# untitled.net
KiCad netlist of a schematic drawn in EAGLE
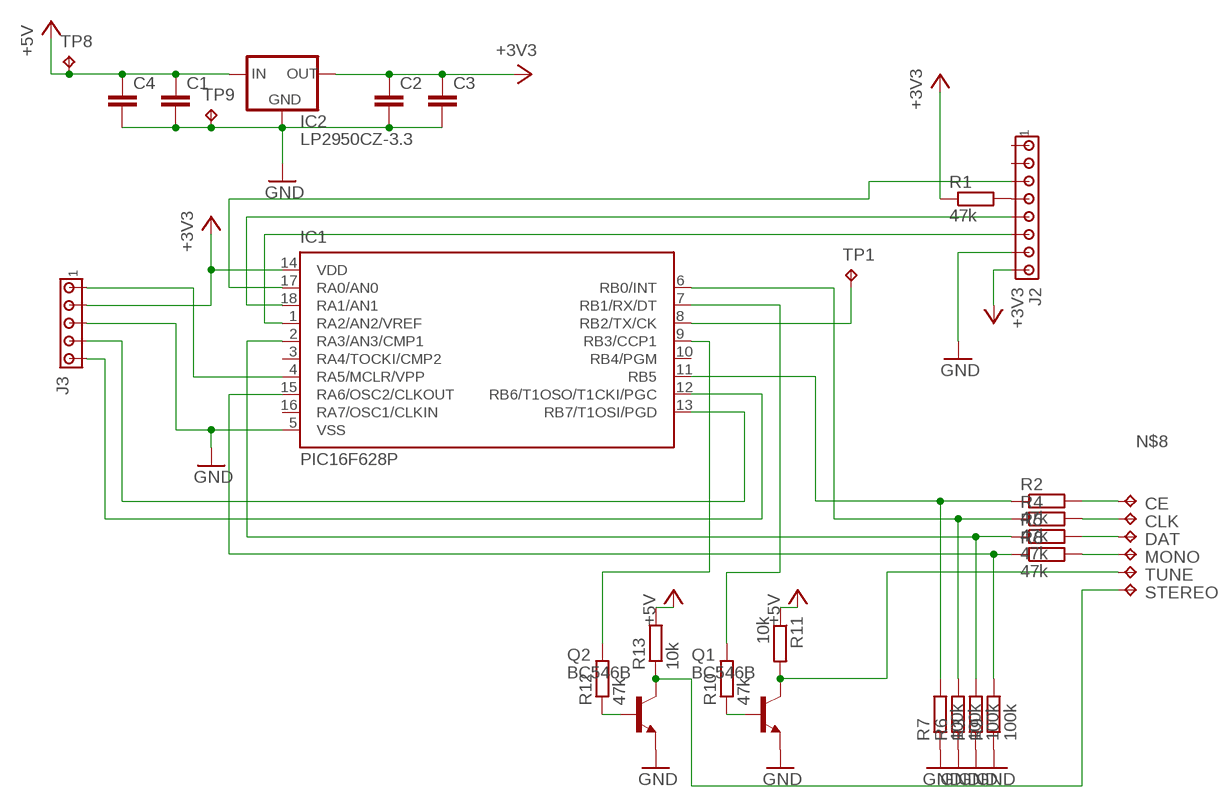
[diagram p0: schematic, sheet 1]

(export (version "E")
  (design (tool "Eeschema 10.0.6"))
  (components
    (comp (ref "C1")
      (value "C-EU025-024X044")
      (footprint "eagle-import:C025-024X044")
      (libsource (lib "eagle-import") (part "C-EU025-024X044"))
    )
    (comp (ref "C2")
      (value "C-EU025-024X044")
      (footprint "eagle-import:C025-024X044")
      (libsource (lib "eagle-import") (part "C-EU025-024X044"))
    )
    (comp (ref "C3")
      (value "C-EU025-024X044")
      (footprint "eagle-import:C025-024X044")
      (libsource (lib "eagle-import") (part "C-EU025-024X044"))
    )
    (comp (ref "C4")
      (value "C-EU025-024X044")
      (footprint "eagle-import:C025-024X044")
      (libsource (lib "eagle-import") (part "C-EU025-024X044"))
    )
    (comp (ref "CE")
      (value "TPB1,27")
      (footprint "eagle-import:B1,27")
      (libsource (lib "eagle-import") (part "TPB1,27"))
    )
    (comp (ref "CLK")
      (value "TPB1,27")
      (footprint "eagle-import:B1,27")
      (libsource (lib "eagle-import") (part "TPB1,27"))
    )
    (comp (ref "DAT")
      (value "TPB1,27")
      (footprint "eagle-import:B1,27")
      (libsource (lib "eagle-import") (part "TPB1,27"))
    )
    (comp (ref "IC1")
      (value "PIC16F628P")
      (footprint "eagle-import:DIL18")
      (fields (field (name "MF") "MICROCHIP") (field (name "MPN") "PIC16F628-04I/P"))
      (libsource (lib "eagle-import") (part "PIC16F62P8"))
    )
    (comp (ref "IC2")
      (value "LP2950CZ-3.3")
      (footprint "eagle-import:TO92")
      (libsource (lib "eagle-import") (part "LP2950?CZ-3.3"))
    )
    (comp (ref "J2")
      (value "MTA08-100")
      (footprint "eagle-import:10X08MTA")
      (libsource (lib "eagle-import") (part "MTA08-100"))
    )
    (comp (ref "J3")
      (value "MTA05-100")
      (footprint "eagle-import:10X05MTA")
      (libsource (lib "eagle-import") (part "MTA05-100"))
    )
    (comp (ref "MONO")
      (value "TPB1,27")
      (footprint "eagle-import:B1,27")
      (libsource (lib "eagle-import") (part "TPB1,27"))
    )
    (comp (ref "Q1")
      (value "BC546B")
      (footprint "eagle-import:TO92-EBC")
      (libsource (lib "eagle-import") (part "BC546B"))
    )
    (comp (ref "Q2")
      (value "BC546B")
      (footprint "eagle-import:TO92-EBC")
      (libsource (lib "eagle-import") (part "BC546B"))
    )
    (comp (ref "R1")
      (value "47k")
      (footprint "eagle-import:0204_7")
      (libsource (lib "eagle-import") (part "R-EU_0204/7"))
    )
    (comp (ref "R2")
      (value "47k")
      (footprint "eagle-import:0204_7")
      (libsource (lib "eagle-import") (part "R-EU_0204/7"))
    )
    (comp (ref "R3")
      (value "100k")
      (footprint "eagle-import:0204_7")
      (libsource (lib "eagle-import") (part "R-EU_0204/7"))
    )
    (comp (ref "R4")
      (value "47k")
      (footprint "eagle-import:0204_7")
      (libsource (lib "eagle-import") (part "R-EU_0204/7"))
    )
    (comp (ref "R5")
      (value "47k")
      (footprint "eagle-import:0204_7")
      (libsource (lib "eagle-import") (part "R-EU_0204/7"))
    )
    (comp (ref "R6")
      (value "100k")
      (footprint "eagle-import:0204_7")
      (libsource (lib "eagle-import") (part "R-EU_0204/7"))
    )
    (comp (ref "R7")
      (value "100k")
      (footprint "eagle-import:0204_7")
      (libsource (lib "eagle-import") (part "R-EU_0204/7"))
    )
    (comp (ref "R8")
      (value "47k")
      (footprint "eagle-import:0204_7")
      (libsource (lib "eagle-import") (part "R-EU_0204/7"))
    )
    (comp (ref "R9")
      (value "100k")
      (footprint "eagle-import:0204_7")
      (libsource (lib "eagle-import") (part "R-EU_0204/7"))
    )
    (comp (ref "R10")
      (value "47k")
      (footprint "eagle-import:0204_7")
      (libsource (lib "eagle-import") (part "R-EU_0204/7"))
    )
    (comp (ref "R11")
      (value "10k")
      (footprint "eagle-import:0204_7")
      (libsource (lib "eagle-import") (part "R-EU_0204/7"))
    )
    (comp (ref "R12")
      (value "47k")
      (footprint "eagle-import:0204_7")
      (libsource (lib "eagle-import") (part "R-EU_0204/7"))
    )
    (comp (ref "R13")
      (value "10k")
      (footprint "eagle-import:0204_7")
      (libsource (lib "eagle-import") (part "R-EU_0204/7"))
    )
    (comp (ref "STEREO")
      (value "TPB1,27")
      (footprint "eagle-import:B1,27")
      (libsource (lib "eagle-import") (part "TPB1,27"))
    )
    (comp (ref "TP1")
      (value "TPB1,27")
      (footprint "eagle-import:B1,27")
      (libsource (lib "eagle-import") (part "TPB1,27"))
    )
    (comp (ref "TP8")
      (value "TPB1,27")
      (footprint "eagle-import:B1,27")
      (libsource (lib "eagle-import") (part "TPB1,27"))
    )
    (comp (ref "TP9")
      (value "TPB1,27")
      (footprint "eagle-import:B1,27")
      (libsource (lib "eagle-import") (part "TPB1,27"))
    )
    (comp (ref "TUNE")
      (value "TPB1,27")
      (footprint "eagle-import:B1,27")
      (libsource (lib "eagle-import") (part "TPB1,27"))
    )
  )
  (nets
    (net (code "1") (name "+3V3") (class "Default")
      (node (ref "C2") (pin "1") (pinfunction "1_1") (pintype "passive"))
      (node (ref "C3") (pin "1") (pinfunction "1_1") (pintype "passive"))
      (node (ref "IC1") (pin "14") (pinfunction "VDD_14") (pintype "power_in"))
      (node (ref "IC2") (pin "1") (pinfunction "OUT_1") (pintype "passive"))
      (node (ref "J2") (pin "8") (pinfunction "8_8") (pintype "passive"))
      (node (ref "J3") (pin "2") (pinfunction "2_2") (pintype "passive"))
      (node (ref "R1") (pin "1") (pinfunction "1_1") (pintype "passive"))
    )
    (net (code "2") (name "+5V") (class "Default")
      (node (ref "C1") (pin "1") (pinfunction "1_1") (pintype "passive"))
      (node (ref "C4") (pin "1") (pinfunction "1_1") (pintype "passive"))
      (node (ref "IC2") (pin "3") (pinfunction "IN_3") (pintype "input"))
      (node (ref "R11") (pin "1") (pinfunction "1_1") (pintype "passive"))
      (node (ref "R13") (pin "2") (pinfunction "2_2") (pintype "passive"))
      (node (ref "TP8") (pin "TP") (pinfunction "TP_TP") (pintype "input"))
    )
    (net (code "3") (name "/N$8") (class "Default")
      (node (ref "CE") (pin "TP") (pinfunction "TP_TP") (pintype "input"))
      (node (ref "R2") (pin "2") (pinfunction "2_2") (pintype "passive"))
    )
    (net (code "4") (name "GND") (class "Default")
      (node (ref "C1") (pin "2") (pinfunction "2_2") (pintype "passive"))
      (node (ref "C2") (pin "2") (pinfunction "2_2") (pintype "passive"))
      (node (ref "C3") (pin "2") (pinfunction "2_2") (pintype "passive"))
      (node (ref "C4") (pin "2") (pinfunction "2_2") (pintype "passive"))
      (node (ref "IC1") (pin "5") (pinfunction "VSS_5") (pintype "power_in"))
      (node (ref "IC2") (pin "2") (pinfunction "GND_2") (pintype "input"))
      (node (ref "J2") (pin "7") (pinfunction "7_7") (pintype "passive"))
      (node (ref "J3") (pin "3") (pinfunction "3_3") (pintype "passive"))
      (node (ref "Q1") (pin "E") (pinfunction "E_E") (pintype "passive"))
      (node (ref "Q2") (pin "E") (pinfunction "E_E") (pintype "passive"))
      (node (ref "R3") (pin "1") (pinfunction "1_1") (pintype "passive"))
      (node (ref "R6") (pin "1") (pinfunction "1_1") (pintype "passive"))
      (node (ref "R7") (pin "1") (pinfunction "1_1") (pintype "passive"))
      (node (ref "R9") (pin "1") (pinfunction "1_1") (pintype "passive"))
      (node (ref "TP9") (pin "TP") (pinfunction "TP_TP") (pintype "input"))
    )
    (net (code "5") (name "Net-(CLK-PadTP)") (class "Default")
      (node (ref "CLK") (pin "TP") (pinfunction "TP_TP") (pintype "input"))
      (node (ref "R4") (pin "2") (pinfunction "2_2") (pintype "passive"))
    )
    (net (code "6") (name "Net-(DAT-PadTP)") (class "Default")
      (node (ref "DAT") (pin "TP") (pinfunction "TP_TP") (pintype "input"))
      (node (ref "R5") (pin "2") (pinfunction "2_2") (pintype "passive"))
    )
    (net (code "7") (name "Net-(IC1-RA0{slash}AN0)") (class "Default")
      (node (ref "IC1") (pin "17") (pinfunction "RA0/AN0_17") (pintype "bidirectional"))
      (node (ref "J2") (pin "3") (pinfunction "3_3") (pintype "passive"))
    )
    (net (code "8") (name "Net-(IC1-RA1{slash}AN1)") (class "Default")
      (node (ref "IC1") (pin "18") (pinfunction "RA1/AN1_18") (pintype "bidirectional"))
      (node (ref "J2") (pin "5") (pinfunction "5_5") (pintype "passive"))
    )
    (net (code "9") (name "Net-(IC1-RA2{slash}AN2{slash}VREF)") (class "Default")
      (node (ref "IC1") (pin "1") (pinfunction "RA2/AN2/VREF_1") (pintype "bidirectional"))
      (node (ref "J2") (pin "6") (pinfunction "6_6") (pintype "passive"))
    )
    (net (code "10") (name "Net-(IC1-RA3{slash}AN3{slash}CMP1)") (class "Default")
      (node (ref "IC1") (pin "2") (pinfunction "RA3/AN3/CMP1_2") (pintype "bidirectional"))
      (node (ref "R3") (pin "2") (pinfunction "2_2") (pintype "passive"))
      (node (ref "R5") (pin "1") (pinfunction "1_1") (pintype "passive"))
    )
    (net (code "11") (name "Net-(IC1-RA5{slash}MCLR{slash}VPP)") (class "Default")
      (node (ref "IC1") (pin "4") (pinfunction "RA5/MCLR/VPP_4") (pintype "bidirectional"))
      (node (ref "J3") (pin "1") (pinfunction "1_1") (pintype "passive"))
    )
    (net (code "12") (name "Net-(IC1-RA6{slash}OSC2{slash}CLKOUT)") (class "Default")
      (node (ref "IC1") (pin "15") (pinfunction "RA6/OSC2/CLKOUT_15") (pintype "bidirectional"))
      (node (ref "R8") (pin "1") (pinfunction "1_1") (pintype "passive"))
      (node (ref "R9") (pin "2") (pinfunction "2_2") (pintype "passive"))
    )
    (net (code "13") (name "Net-(IC1-RB0{slash}INT)") (class "Default")
      (node (ref "IC1") (pin "6") (pinfunction "RB0/INT_6") (pintype "bidirectional"))
      (node (ref "R4") (pin "1") (pinfunction "1_1") (pintype "passive"))
      (node (ref "R6") (pin "2") (pinfunction "2_2") (pintype "passive"))
    )
    (net (code "14") (name "Net-(IC1-RB1{slash}RX{slash}DT)") (class "Default")
      (node (ref "IC1") (pin "7") (pinfunction "RB1/RX/DT_7") (pintype "bidirectional"))
      (node (ref "R10") (pin "2") (pinfunction "2_2") (pintype "passive"))
    )
    (net (code "15") (name "Net-(IC1-RB2{slash}TX{slash}CK)") (class "Default")
      (node (ref "IC1") (pin "8") (pinfunction "RB2/TX/CK_8") (pintype "bidirectional"))
      (node (ref "TP1") (pin "TP") (pinfunction "TP_TP") (pintype "input"))
    )
    (net (code "16") (name "Net-(IC1-RB3{slash}CCP1)") (class "Default")
      (node (ref "IC1") (pin "9") (pinfunction "RB3/CCP1_9") (pintype "bidirectional"))
      (node (ref "R12") (pin "2") (pinfunction "2_2") (pintype "passive"))
    )
    (net (code "17") (name "Net-(IC1-RB5)") (class "Default")
      (node (ref "IC1") (pin "11") (pinfunction "RB5_11") (pintype "bidirectional"))
      (node (ref "R2") (pin "1") (pinfunction "1_1") (pintype "passive"))
      (node (ref "R7") (pin "2") (pinfunction "2_2") (pintype "passive"))
    )
    (net (code "18") (name "Net-(IC1-RB6{slash}T1OSO{slash}T1CKI{slash}PGC)") (class "Default")
      (node (ref "IC1") (pin "12") (pinfunction "RB6/T1OSO/T1CKI/PGC_12") (pintype "bidirectional"))
      (node (ref "J3") (pin "5") (pinfunction "5_5") (pintype "passive"))
    )
    (net (code "19") (name "Net-(IC1-RB7{slash}T1OSI{slash}PGD)") (class "Default")
      (node (ref "IC1") (pin "13") (pinfunction "RB7/T1OSI/PGD_13") (pintype "bidirectional"))
      (node (ref "J3") (pin "4") (pinfunction "4_4") (pintype "passive"))
    )
    (net (code "20") (name "Net-(J2-Pad4)") (class "Default")
      (node (ref "J2") (pin "4") (pinfunction "4_4") (pintype "passive"))
      (node (ref "R1") (pin "2") (pinfunction "2_2") (pintype "passive"))
    )
    (net (code "21") (name "Net-(MONO-PadTP)") (class "Default")
      (node (ref "MONO") (pin "TP") (pinfunction "TP_TP") (pintype "input"))
      (node (ref "R8") (pin "2") (pinfunction "2_2") (pintype "passive"))
    )
    (net (code "22") (name "Net-(Q1-PadB)") (class "Default")
      (node (ref "Q1") (pin "B") (pinfunction "B_B") (pintype "passive"))
      (node (ref "R10") (pin "1") (pinfunction "1_1") (pintype "passive"))
    )
    (net (code "23") (name "Net-(Q1-PadC)") (class "Default")
      (node (ref "Q1") (pin "C") (pinfunction "C_C") (pintype "passive"))
      (node (ref "R11") (pin "2") (pinfunction "2_2") (pintype "passive"))
      (node (ref "TUNE") (pin "TP") (pinfunction "TP_TP") (pintype "input"))
    )
    (net (code "24") (name "Net-(Q2-PadB)") (class "Default")
      (node (ref "Q2") (pin "B") (pinfunction "B_B") (pintype "passive"))
      (node (ref "R12") (pin "1") (pinfunction "1_1") (pintype "passive"))
    )
    (net (code "25") (name "Net-(Q2-PadC)") (class "Default")
      (node (ref "Q2") (pin "C") (pinfunction "C_C") (pintype "passive"))
      (node (ref "R13") (pin "1") (pinfunction "1_1") (pintype "passive"))
      (node (ref "STEREO") (pin "TP") (pinfunction "TP_TP") (pintype "input"))
    )
    (net (code "26") (name "unconnected-(IC1-RA4{slash}TOCKI{slash}CMP2-Pad3)") (class "Default")
      (node (ref "IC1") (pin "3") (pinfunction "RA4/TOCKI/CMP2_3") (pintype "bidirectional"))
    )
    (net (code "27") (name "unconnected-(IC1-RA7{slash}OSC1{slash}CLKIN-Pad16)") (class "Default")
      (node (ref "IC1") (pin "16") (pinfunction "RA7/OSC1/CLKIN_16") (pintype "bidirectional"))
    )
    (net (code "28") (name "unconnected-(IC1-RB4{slash}PGM-Pad10)") (class "Default")
      (node (ref "IC1") (pin "10") (pinfunction "RB4/PGM_10") (pintype "bidirectional"))
    )
    (net (code "29") (name "unconnected-(J2-Pad1)") (class "Default")
      (node (ref "J2") (pin "1") (pinfunction "1_1") (pintype "passive"))
    )
    (net (code "30") (name "unconnected-(J2-Pad2)") (class "Default")
      (node (ref "J2") (pin "2") (pinfunction "2_2") (pintype "passive"))
    )
  )
)
